# RK3562-VCCIO6.net
KiCad netlist of a schematic drawn in Altium Designer
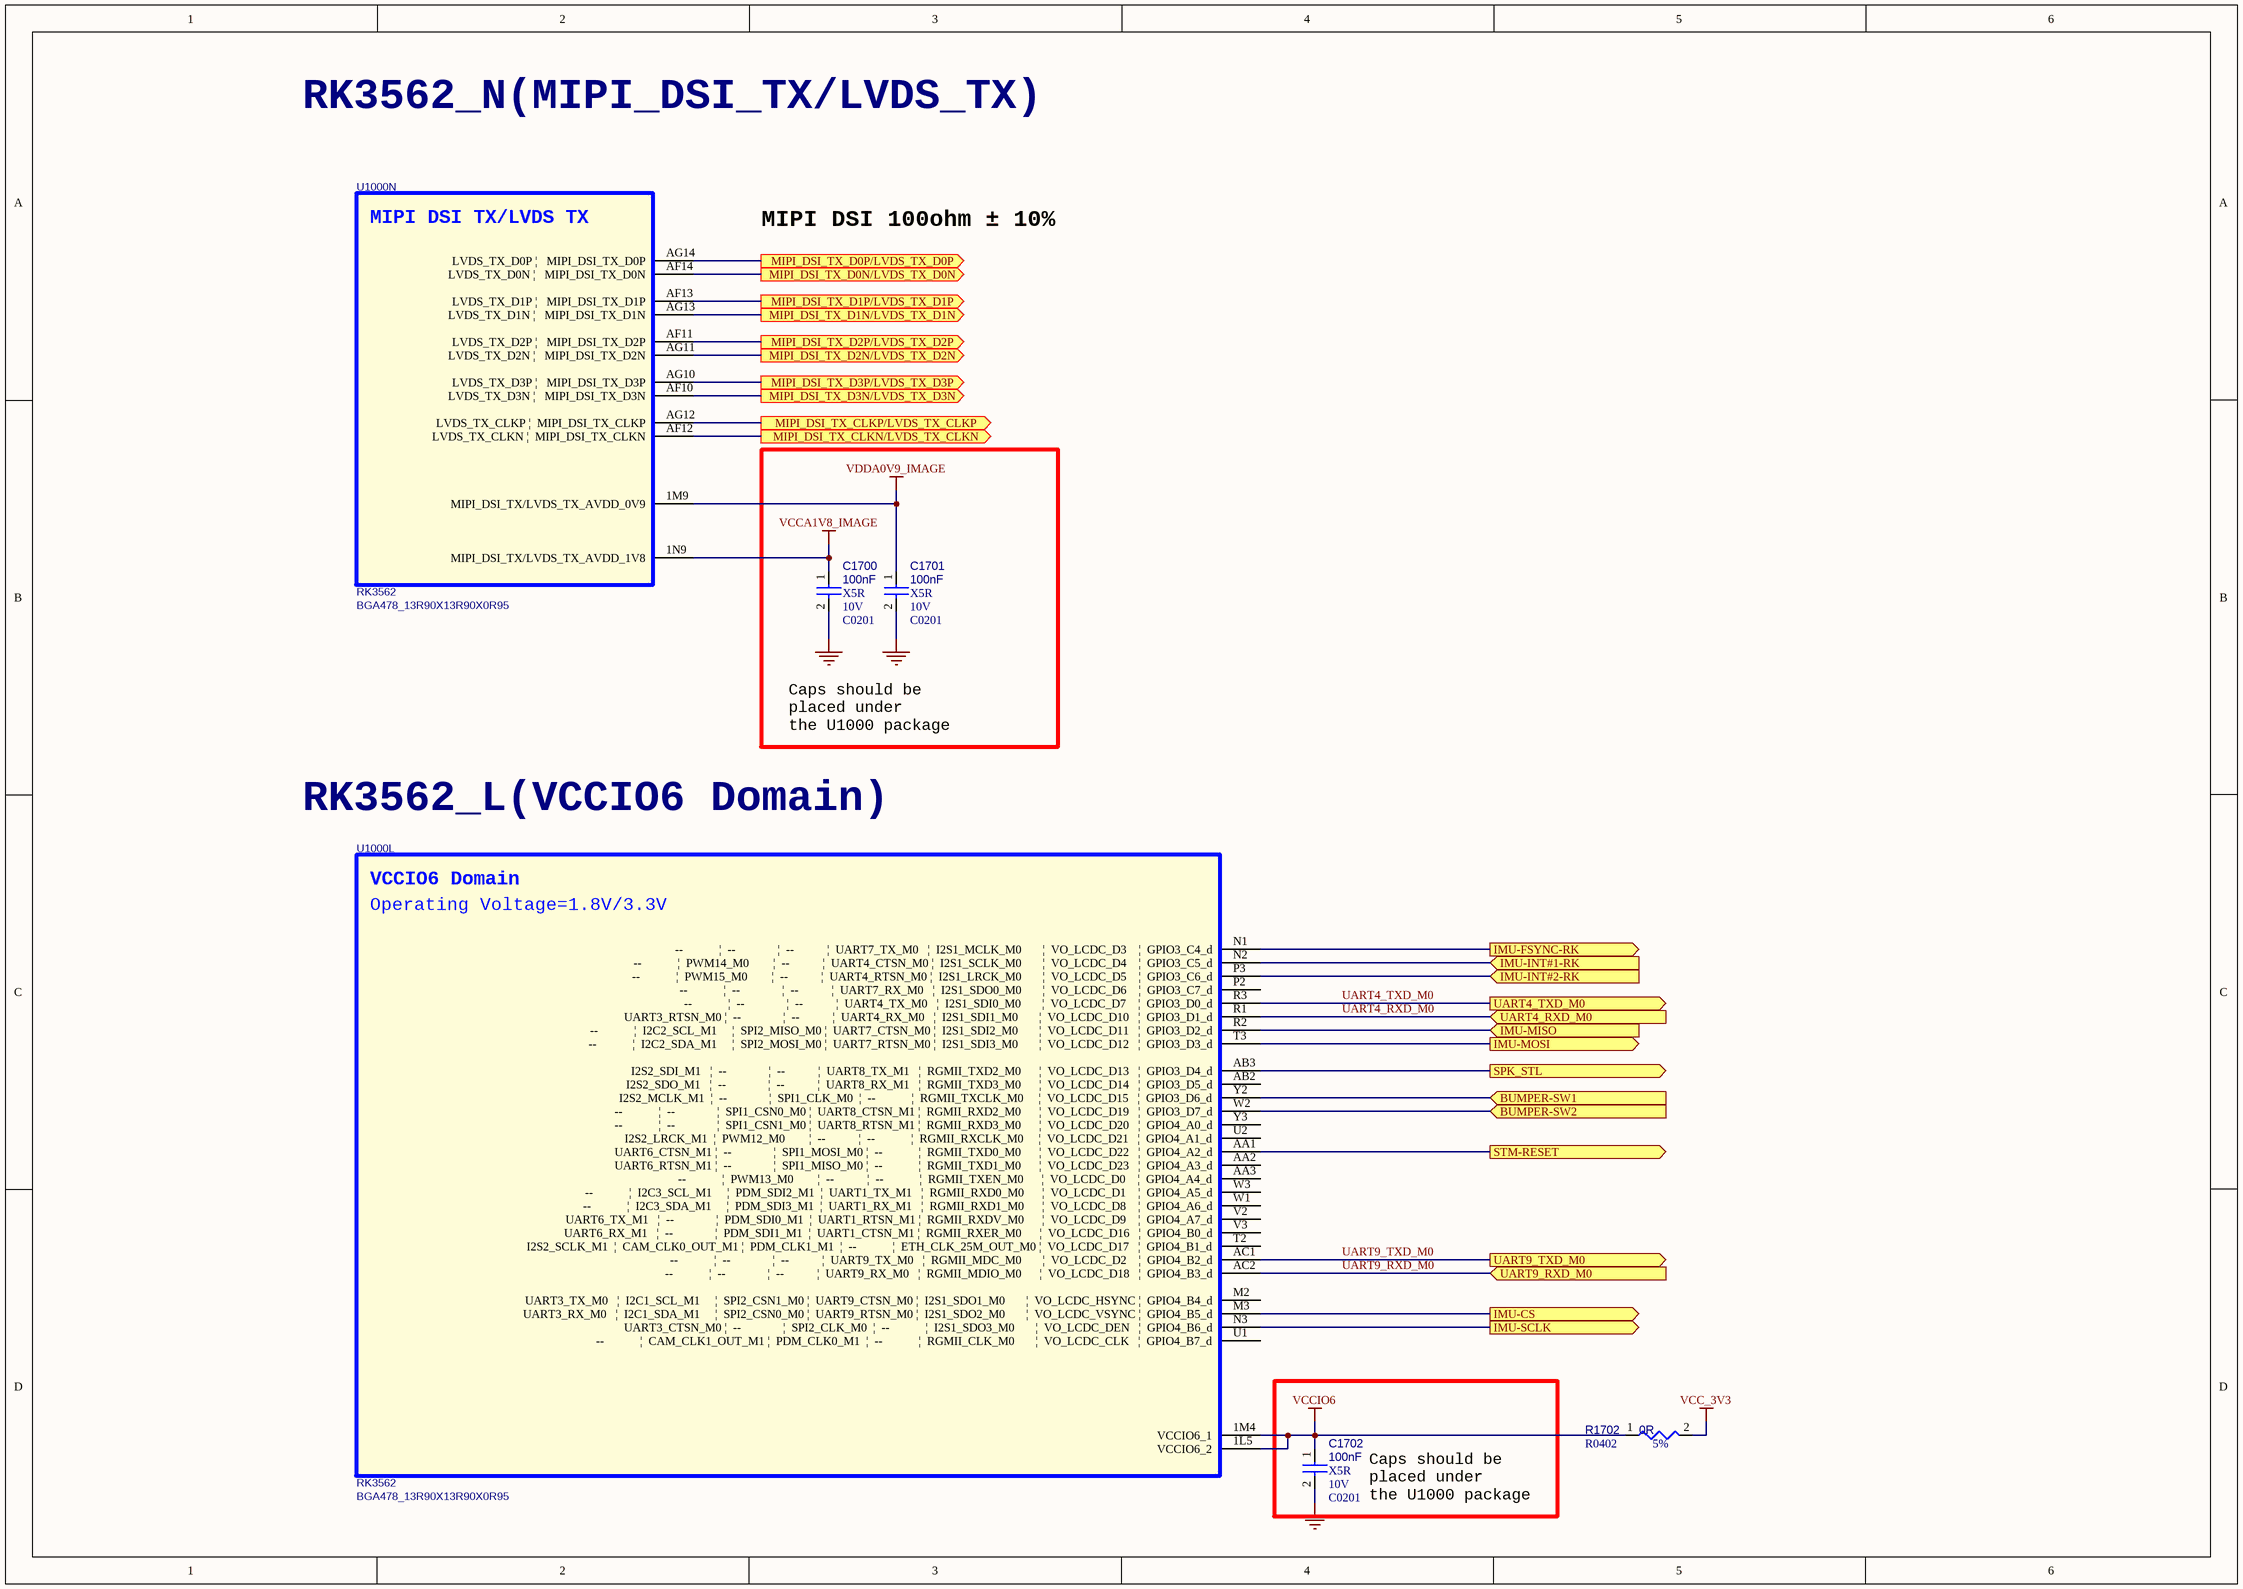
[diagram p0: RK3562-VCCIO6.SchDoc]

(export (version "E")
  (design (tool "Eeschema 10.0.6"))
  (components
    (comp (ref "C1700")
      (value "100nF")
      (footprint "C0201")
      (description "cap,100.00nF,+/-10%,10V,X5R,C0201")
      (fields
        (field (name "DIELECTRIC") "X5R")
        (field (name "PCB FOOTPRINT") "C0201")
        (field (name "VOLTAGE") "10V")
        (field (name "MANUFACTURER") "TDK")
        (field (name "TOLERANCE") "10%")
        (field (name "CREATED BY") "JJJ")
      )
      (libsource (lib "RK3562_REF") (part "CAP NP"))
    )
    (comp (ref "C1701")
      (value "100nF")
      (footprint "C0201")
      (description "cap,100.00nF,+/-10%,10V,X5R,C0201")
      (fields
        (field (name "DIELECTRIC") "X5R")
        (field (name "PCB FOOTPRINT") "C0201")
        (field (name "VOLTAGE") "10V")
        (field (name "TOLERANCE") "10%")
        (field (name "MANUFACTURER") "TDK")
        (field (name "CREATED BY") "JJJ")
      )
      (libsource (lib "RK3562_REF") (part "CAP NP"))
    )
    (comp (ref "C1702")
      (value "100nF")
      (footprint "C0201")
      (description "cap,100.00nF,+/-10%,10V,X5R,C0201")
      (fields
        (field (name "DIELECTRIC") "X5R")
        (field (name "PCB FOOTPRINT") "C0201")
        (field (name "VOLTAGE") "10V")
        (field (name "MANUFACTURER") "TDK")
        (field (name "TOLERANCE") "10%")
        (field (name "CREATED BY") "JJJ")
      )
      (libsource (lib "RK3562_REF") (part "CAP NP"))
    )
    (comp (ref "R1702")
      (value "0R")
      (footprint "R0402")
      (description "通用厚膜电阻,0R,+/-5%,R0402,1/16W.")
      (fields
        (field (name "TOLERANCE") "5%")
        (field (name "PCB FOOTPRINT") "R0402")
        (field (name "MANUFACTURER") "YAGEO")
        (field (name "CREATED BY") "YTL")
      )
      (libsource (lib "RK3562_REF") (part "RESISTOR"))
    )
    (comp (ref "U1000")
      (value "RK3562")
      (footprint "BGA478_13R90X13R90X0R95")
      (description "ROCKCHIP SOC")
      (fields
        (field (name "PCB FOOTPRINT") "BGA478_13R90X13R90X0R95")
        (field (name "MANUFACTURER") "Rockchip (瑞芯微)")
        (field (name "CREATED BY") "JJJ")
      )
      (libsource (lib "RK3562_REF") (part "SOC_RK3562"))
    )
  )
  (nets
    (net (code "1") (name "/BUMPER-SW1") (class "Default")
      (node (ref "U1000") (pin "Y2") (pinfunction "I2S2_MCLK_M1__¦__--______________¦__SPI1_CLK_M0__¦__--____________¦__RGMII_TXCLK_M0_____¦__VO_LCDC_D15___¦__GPIO3_D6_d_Y2") (pintype "passive"))
    )
    (net (code "2") (name "/BUMPER-SW2") (class "Default")
      (node (ref "U1000") (pin "W2") (pinfunction "--____________¦__--______________¦__SPI1_CSN0_M0_¦__UART8_CTSN_M1_¦__RGMII_RXD2_M0______¦__VO_LCDC_D19___¦__GPIO3_D7_d_W2") (pintype "passive"))
    )
    (net (code "3") (name "/IMU-CS") (class "Default")
      (node (ref "U1000") (pin "M3") (pinfunction "UART3_RX_M0___¦__I2C1_SDA_M1_____¦__SPI2_CSN0_M0_¦__UART9_RTSN_M0_¦__I2S1_SDO2_M0_______¦__VO_LCDC_VSYNC_¦__GPIO4_B5_d_M3") (pintype "passive"))
    )
    (net (code "4") (name "/IMU-FSYNC-RK") (class "Default")
      (node (ref "U1000") (pin "N1") (pinfunction "--____________¦__--______________¦__--___________¦__UART7_TX_M0___¦__I2S1_MCLK_M0_______¦__VO_LCDC_D3____¦__GPIO3_C4_d_N1") (pintype "passive"))
    )
    (net (code "5") (name "/IMU-INT#1-RK") (class "Default")
      (node (ref "U1000") (pin "N2") (pinfunction "--____________¦__PWM14_M0________¦__--___________¦__UART4_CTSN_M0_¦__I2S1_SCLK_M0_______¦__VO_LCDC_D4____¦__GPIO3_C5_d_N2") (pintype "passive"))
    )
    (net (code "6") (name "/IMU-INT#2-RK") (class "Default")
      (node (ref "U1000") (pin "P3") (pinfunction "--____________¦__PWM15_M0________¦__--___________¦__UART4_RTSN_M0_¦__I2S1_LRCK_M0_______¦__VO_LCDC_D5____¦__GPIO3_C6_d_P3") (pintype "passive"))
    )
    (net (code "7") (name "/IMU-MISO") (class "Default")
      (node (ref "U1000") (pin "R2") (pinfunction "--____________¦__I2C2_SCL_M1_____¦__SPI2_MISO_M0_¦__UART7_CTSN_M0_¦__I2S1_SDI2_M0_______¦__VO_LCDC_D11___¦__GPIO3_D2_d_R2") (pintype "passive"))
    )
    (net (code "8") (name "/IMU-MOSI") (class "Default")
      (node (ref "U1000") (pin "T3") (pinfunction "--____________¦__I2C2_SDA_M1_____¦__SPI2_MOSI_M0_¦__UART7_RTSN_M0_¦__I2S1_SDI3_M0_______¦__VO_LCDC_D12___¦__GPIO3_D3_d_T3") (pintype "passive"))
    )
    (net (code "9") (name "/IMU-SCLK") (class "Default")
      (node (ref "U1000") (pin "N3") (pinfunction "UART3_CTSN_M0_¦__--______________¦__SPI2_CLK_M0__¦__--____________¦__I2S1_SDO3_M0_______¦__VO_LCDC_DEN___¦__GPIO4_B6_d_N3") (pintype "passive"))
    )
    (net (code "10") (name "/MIPI_DSI_TX_CLKN{slash}LVDS_TX_CLKN") (class "Default")
      (node (ref "U1000") (pin "AF12") (pinfunction "LVDS_TX_CLKN_¦__MIPI_DSI_TX_CLKN_AF12") (pintype "passive"))
    )
    (net (code "11") (name "/MIPI_DSI_TX_CLKP{slash}LVDS_TX_CLKP") (class "Default")
      (node (ref "U1000") (pin "AG12") (pinfunction "LVDS_TX_CLKP_¦__MIPI_DSI_TX_CLKP_AG12") (pintype "passive"))
    )
    (net (code "12") (name "/MIPI_DSI_TX_D0N{slash}LVDS_TX_D0N") (class "Default")
      (node (ref "U1000") (pin "AF14") (pinfunction "LVDS_TX_D0N_¦___MIPI_DSI_TX_D0N_AF14") (pintype "passive"))
    )
    (net (code "13") (name "/MIPI_DSI_TX_D0P{slash}LVDS_TX_D0P") (class "Default")
      (node (ref "U1000") (pin "AG14") (pinfunction "LVDS_TX_D0P_¦___MIPI_DSI_TX_D0P_AG14") (pintype "passive"))
    )
    (net (code "14") (name "/MIPI_DSI_TX_D1N{slash}LVDS_TX_D1N") (class "Default")
      (node (ref "U1000") (pin "AG13") (pinfunction "LVDS_TX_D1N_¦___MIPI_DSI_TX_D1N_AG13") (pintype "passive"))
    )
    (net (code "15") (name "/MIPI_DSI_TX_D1P{slash}LVDS_TX_D1P") (class "Default")
      (node (ref "U1000") (pin "AF13") (pinfunction "LVDS_TX_D1P_¦___MIPI_DSI_TX_D1P_AF13") (pintype "passive"))
    )
    (net (code "16") (name "/MIPI_DSI_TX_D2N{slash}LVDS_TX_D2N") (class "Default")
      (node (ref "U1000") (pin "AG11") (pinfunction "LVDS_TX_D2N_¦___MIPI_DSI_TX_D2N_AG11") (pintype "passive"))
    )
    (net (code "17") (name "/MIPI_DSI_TX_D2P{slash}LVDS_TX_D2P") (class "Default")
      (node (ref "U1000") (pin "AF11") (pinfunction "LVDS_TX_D2P_¦___MIPI_DSI_TX_D2P_AF11") (pintype "passive"))
    )
    (net (code "18") (name "/MIPI_DSI_TX_D3N{slash}LVDS_TX_D3N") (class "Default")
      (node (ref "U1000") (pin "AF10") (pinfunction "LVDS_TX_D3N_¦___MIPI_DSI_TX_D3N_AF10") (pintype "passive"))
    )
    (net (code "19") (name "/MIPI_DSI_TX_D3P{slash}LVDS_TX_D3P") (class "Default")
      (node (ref "U1000") (pin "AG10") (pinfunction "LVDS_TX_D3P_¦___MIPI_DSI_TX_D3P_AG10") (pintype "passive"))
    )
    (net (code "20") (name "/SPK_STL") (class "Default")
      (node (ref "U1000") (pin "AB3") (pinfunction "I2S2_SDI_M1___¦__--______________¦__--___________¦__UART8_TX_M1___¦__RGMII_TXD2_M0______¦__VO_LCDC_D13___¦__GPIO3_D4_d_AB3") (pintype "passive"))
    )
    (net (code "21") (name "/STM-RESET") (class "Default")
      (node (ref "U1000") (pin "AA1") (pinfunction "UART6_CTSN_M1_¦__--______________¦__SPI1_MOSI_M0_¦__--____________¦__RGMII_TXD0_M0______¦__VO_LCDC_D22___¦__GPIO4_A2_d_AA1") (pintype "passive"))
    )
    (net (code "22") (name "/UART4_RXD_M0") (class "Default")
      (node (ref "U1000") (pin "R1") (pinfunction "UART3_RTSN_M0_¦__--______________¦__--___________¦__UART4_RX_M0___¦__I2S1_SDI1_M0_______¦__VO_LCDC_D10___¦__GPIO3_D1_d_R1") (pintype "passive"))
    )
    (net (code "23") (name "/UART4_TXD_M0") (class "Default")
      (node (ref "U1000") (pin "R3") (pinfunction "--____________¦__--______________¦__--___________¦__UART4_TX_M0___¦__I2S1_SDI0_M0_______¦__VO_LCDC_D7____¦__GPIO3_D0_d_R3") (pintype "passive"))
    )
    (net (code "24") (name "/UART9_RXD_M0") (class "Default")
      (node (ref "U1000") (pin "AC2") (pinfunction "--____________¦__--______________¦__--___________¦__UART9_RX_M0___¦__RGMII_MDIO_M0______¦__VO_LCDC_D18___¦__GPIO4_B3_d_AC2") (pintype "passive"))
    )
    (net (code "25") (name "/UART9_TXD_M0") (class "Default")
      (node (ref "U1000") (pin "AC1") (pinfunction "--____________¦__--______________¦__--___________¦__UART9_TX_M0___¦__RGMII_MDC_M0_______¦__VO_LCDC_D2____¦__GPIO4_B2_d_AC1") (pintype "passive"))
    )
    (net (code "26") (name "GND") (class "Default")
      (node (ref "C1700") (pin "2") (pinfunction "2_2") (pintype "passive"))
      (node (ref "C1701") (pin "2") (pinfunction "2_2") (pintype "passive"))
      (node (ref "C1702") (pin "2") (pinfunction "2_2") (pintype "passive"))
    )
    (net (code "27") (name "VCCA1V8_IMAGE") (class "Default")
      (node (ref "C1700") (pin "1") (pinfunction "1_1") (pintype "passive"))
      (node (ref "U1000") (pin "1N9") (pinfunction "MIPI_DSI_TX/LVDS_TX_AVDD_1V8_1N9") (pintype "passive"))
    )
    (net (code "28") (name "VCCIO6") (class "Default")
      (node (ref "C1702") (pin "1") (pinfunction "1_1") (pintype "passive"))
      (node (ref "R1702") (pin "1") (pinfunction "1_1") (pintype "passive"))
      (node (ref "U1000") (pin "1L5") (pinfunction "VCCIO6_2_1L5") (pintype "passive"))
      (node (ref "U1000") (pin "1M4") (pinfunction "VCCIO6_1_1M4") (pintype "passive"))
    )
    (net (code "29") (name "VCC_3V3") (class "Default")
      (node (ref "R1702") (pin "2") (pinfunction "2_2") (pintype "passive"))
    )
    (net (code "30") (name "VDDA0V9_IMAGE") (class "Default")
      (node (ref "C1701") (pin "1") (pinfunction "1_1") (pintype "passive"))
      (node (ref "U1000") (pin "1M9") (pinfunction "MIPI_DSI_TX/LVDS_TX_AVDD_0V9_1M9") (pintype "passive"))
    )
    (net (code "31") (name "unconnected-(U1000L---____________¦__--______________¦__--___________¦__UART7_RX_M0___¦__I2S1_SDO0_M0_______¦__VO_LCDC_D6____¦__GPIO3_C7_d-PadP2)") (class "Default")
      (node (ref "U1000") (pin "P2") (pinfunction "--____________¦__--______________¦__--___________¦__UART7_RX_M0___¦__I2S1_SDO0_M0_______¦__VO_LCDC_D6____¦__GPIO3_C7_d_P2") (pintype "passive"))
    )
    (net (code "32") (name "unconnected-(U1000L---____________¦__--______________¦__SPI1_CSN1_M0_¦__UART8_RTSN_M1_¦__RGMII_RXD3_M0______¦__VO_LCDC_D20___¦__GPIO4_A0_d-PadY3)") (class "Default")
      (node (ref "U1000") (pin "Y3") (pinfunction "--____________¦__--______________¦__SPI1_CSN1_M0_¦__UART8_RTSN_M1_¦__RGMII_RXD3_M0______¦__VO_LCDC_D20___¦__GPIO4_A0_d_Y3") (pintype "passive"))
    )
    (net (code "33") (name "unconnected-(U1000L---____________¦__CAM_CLK1_OUT_M1_¦__PDM_CLK0_M1__¦__--____________¦__RGMII_CLK_M0_______¦__VO_LCDC_CLK___¦__GPIO4_B7_d-PadU1)") (class "Default")
      (node (ref "U1000") (pin "U1") (pinfunction "--____________¦__CAM_CLK1_OUT_M1_¦__PDM_CLK0_M1__¦__--____________¦__RGMII_CLK_M0_______¦__VO_LCDC_CLK___¦__GPIO4_B7_d_U1") (pintype "passive"))
    )
    (net (code "34") (name "unconnected-(U1000L---____________¦__I2C3_SCL_M1_____¦__PDM_SDI2_M1__¦__UART1_TX_M1___¦__RGMII_RXD0_M0______¦__VO_LCDC_D1____¦__GPIO4_A5_d-PadW3)") (class "Default")
      (node (ref "U1000") (pin "W3") (pinfunction "--____________¦__I2C3_SCL_M1_____¦__PDM_SDI2_M1__¦__UART1_TX_M1___¦__RGMII_RXD0_M0______¦__VO_LCDC_D1____¦__GPIO4_A5_d_W3") (pintype "passive"))
    )
    (net (code "35") (name "unconnected-(U1000L---____________¦__I2C3_SDA_M1_____¦__PDM_SDI3_M1__¦__UART1_RX_M1___¦__RGMII_RXD1_M0______¦__VO_LCDC_D8____¦__GPIO4_A6_d-PadW1)") (class "Default")
      (node (ref "U1000") (pin "W1") (pinfunction "--____________¦__I2C3_SDA_M1_____¦__PDM_SDI3_M1__¦__UART1_RX_M1___¦__RGMII_RXD1_M0______¦__VO_LCDC_D8____¦__GPIO4_A6_d_W1") (pintype "passive"))
    )
    (net (code "36") (name "unconnected-(U1000L---____________¦__PWM13_M0________¦__--___________¦__--____________¦__RGMII_TXEN_M0______¦__VO_LCDC_D0____¦__GPIO4_A4_d-PadAA3)") (class "Default")
      (node (ref "U1000") (pin "AA3") (pinfunction "--____________¦__PWM13_M0________¦__--___________¦__--____________¦__RGMII_TXEN_M0______¦__VO_LCDC_D0____¦__GPIO4_A4_d_AA3") (pintype "passive"))
    )
    (net (code "37") (name "unconnected-(U1000L-I2S2_LRCK_M1__¦__PWM12_M0________¦__--___________¦__--____________¦__RGMII_RXCLK_M0_____¦__VO_LCDC_D21___¦__GPIO4_A1_d-PadU2)") (class "Default")
      (node (ref "U1000") (pin "U2") (pinfunction "I2S2_LRCK_M1__¦__PWM12_M0________¦__--___________¦__--____________¦__RGMII_RXCLK_M0_____¦__VO_LCDC_D21___¦__GPIO4_A1_d_U2") (pintype "passive"))
    )
    (net (code "38") (name "unconnected-(U1000L-I2S2_SCLK_M1__¦__CAM_CLK0_OUT_M1_¦__PDM_CLK1_M1__¦__--____________¦__ETH_CLK_25M_OUT_M0_¦__VO_LCDC_D17___¦__GPIO4_B1_d-PadT2)") (class "Default")
      (node (ref "U1000") (pin "T2") (pinfunction "I2S2_SCLK_M1__¦__CAM_CLK0_OUT_M1_¦__PDM_CLK1_M1__¦__--____________¦__ETH_CLK_25M_OUT_M0_¦__VO_LCDC_D17___¦__GPIO4_B1_d_T2") (pintype "passive"))
    )
    (net (code "39") (name "unconnected-(U1000L-I2S2_SDO_M1___¦__--______________¦__--___________¦__UART8_RX_M1___¦__RGMII_TXD3_M0______¦__VO_LCDC_D14___¦__GPIO3_D5_d-PadAB2)") (class "Default")
      (node (ref "U1000") (pin "AB2") (pinfunction "I2S2_SDO_M1___¦__--______________¦__--___________¦__UART8_RX_M1___¦__RGMII_TXD3_M0______¦__VO_LCDC_D14___¦__GPIO3_D5_d_AB2") (pintype "passive"))
    )
    (net (code "40") (name "unconnected-(U1000L-UART3_TX_M0___¦__I2C1_SCL_M1_____¦__SPI2_CSN1_M0_¦__UART9_CTSN_M0_¦__I2S1_SDO1_M0_______¦__VO_LCDC_HSYNC_¦__GPIO4_B4_d-PadM2)") (class "Default")
      (node (ref "U1000") (pin "M2") (pinfunction "UART3_TX_M0___¦__I2C1_SCL_M1_____¦__SPI2_CSN1_M0_¦__UART9_CTSN_M0_¦__I2S1_SDO1_M0_______¦__VO_LCDC_HSYNC_¦__GPIO4_B4_d_M2") (pintype "passive"))
    )
    (net (code "41") (name "unconnected-(U1000L-UART6_RTSN_M1_¦__--______________¦__SPI1_MISO_M0_¦__--____________¦__RGMII_TXD1_M0______¦__VO_LCDC_D23___¦__GPIO4_A3_d-PadAA2)") (class "Default")
      (node (ref "U1000") (pin "AA2") (pinfunction "UART6_RTSN_M1_¦__--______________¦__SPI1_MISO_M0_¦__--____________¦__RGMII_TXD1_M0______¦__VO_LCDC_D23___¦__GPIO4_A3_d_AA2") (pintype "passive"))
    )
    (net (code "42") (name "unconnected-(U1000L-UART6_RX_M1___¦__--______________¦__PDM_SDI1_M1__¦__UART1_CTSN_M1_¦__RGMII_RXER_M0______¦__VO_LCDC_D16___¦__GPIO4_B0_d-PadV3)") (class "Default")
      (node (ref "U1000") (pin "V3") (pinfunction "UART6_RX_M1___¦__--______________¦__PDM_SDI1_M1__¦__UART1_CTSN_M1_¦__RGMII_RXER_M0______¦__VO_LCDC_D16___¦__GPIO4_B0_d_V3") (pintype "passive"))
    )
    (net (code "43") (name "unconnected-(U1000L-UART6_TX_M1___¦__--______________¦__PDM_SDI0_M1__¦__UART1_RTSN_M1_¦__RGMII_RXDV_M0______¦__VO_LCDC_D9____¦__GPIO4_A7_d-PadV2)") (class "Default")
      (node (ref "U1000") (pin "V2") (pinfunction "UART6_TX_M1___¦__--______________¦__PDM_SDI0_M1__¦__UART1_RTSN_M1_¦__RGMII_RXDV_M0______¦__VO_LCDC_D9____¦__GPIO4_A7_d_V2") (pintype "passive"))
    )
  )
)
